# PowerSupply.net
KiCad netlist of a schematic drawn in Altium Designer
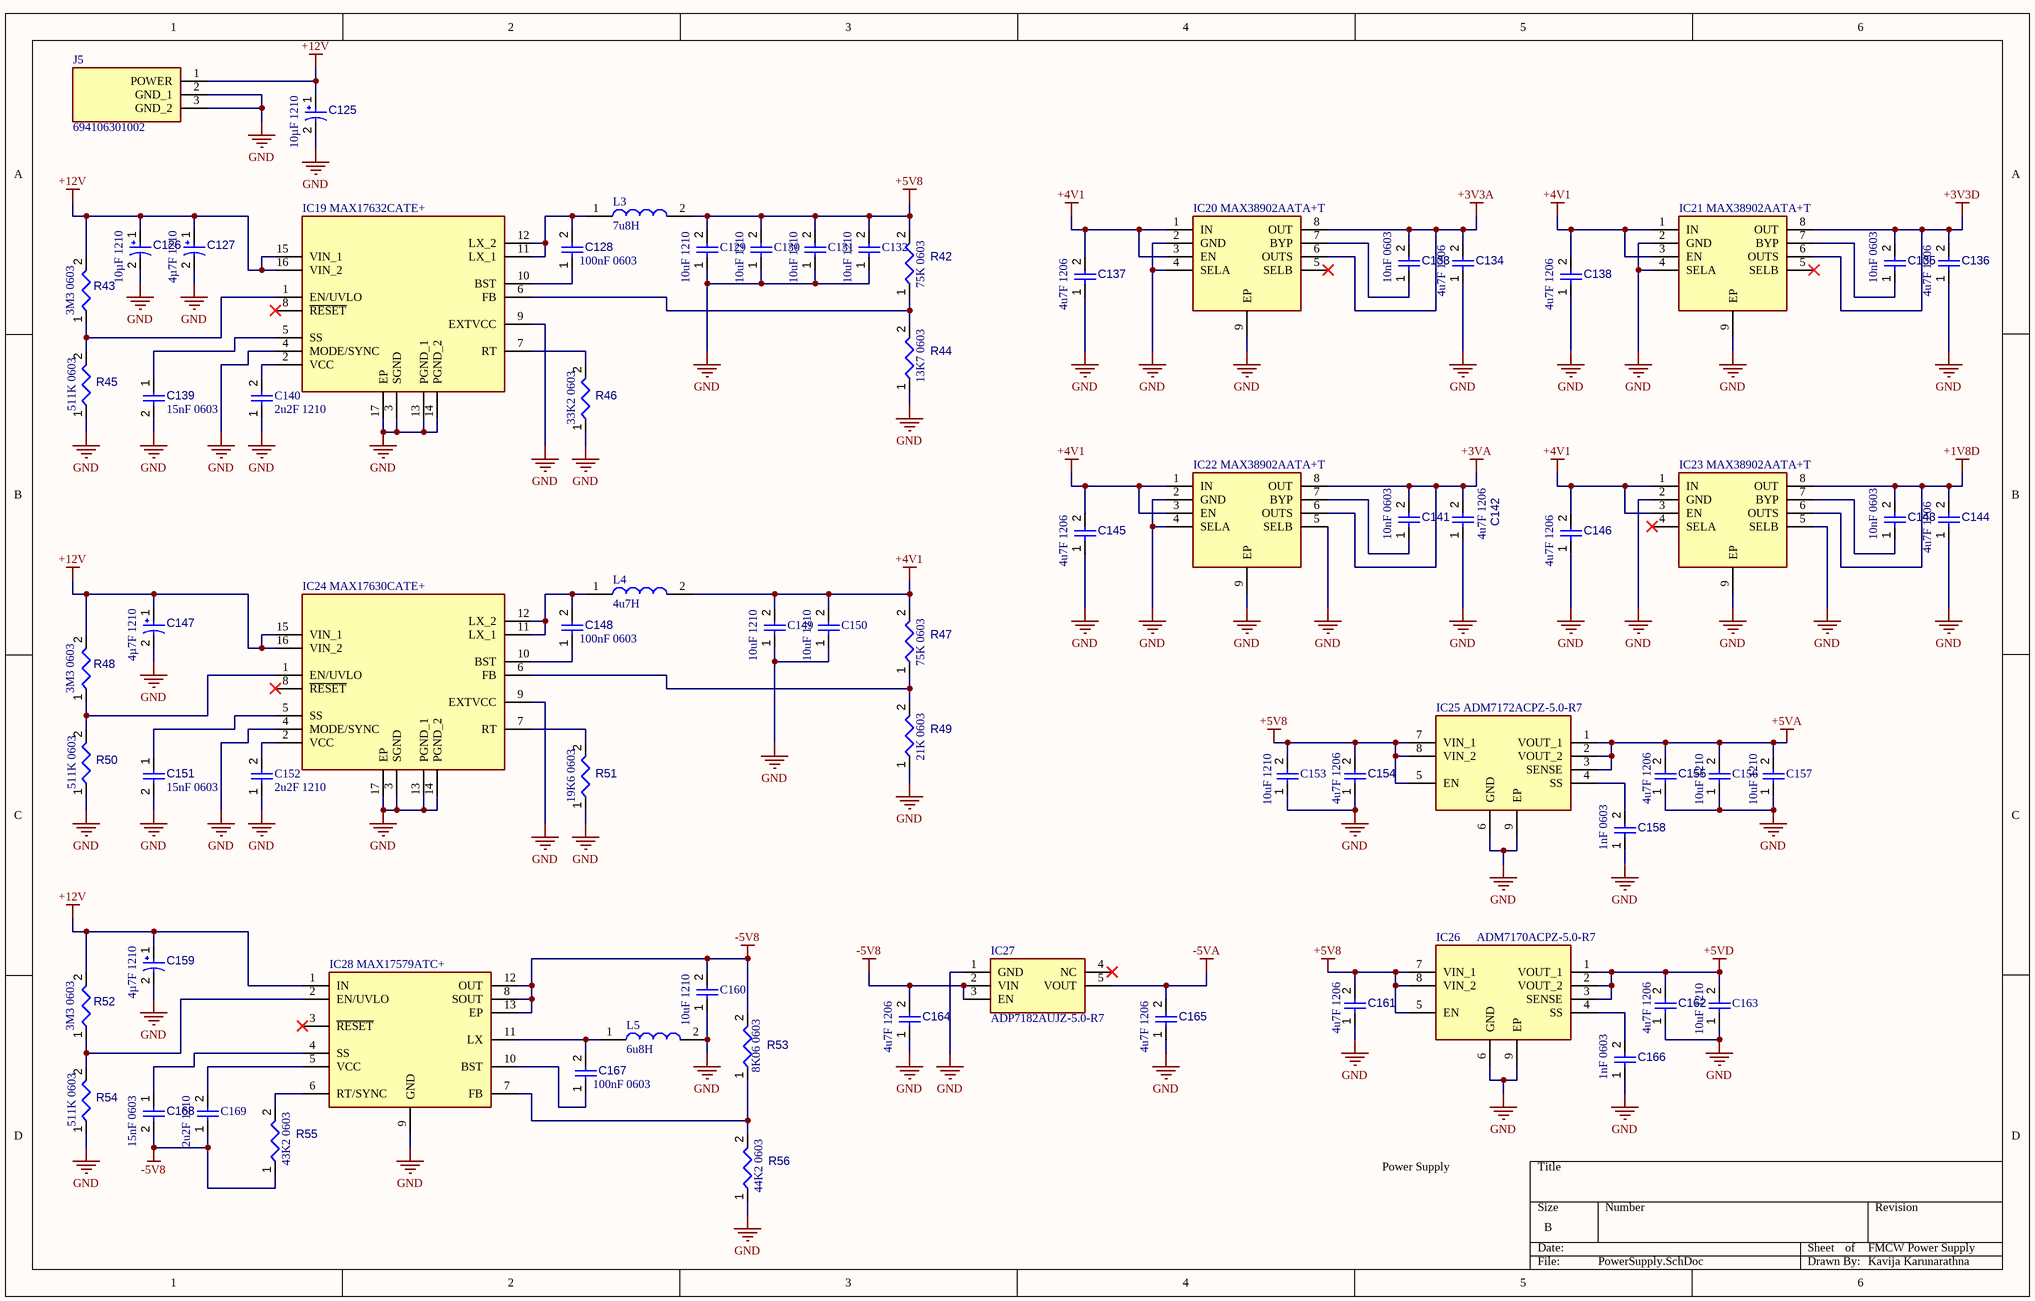
[diagram p0: PowerSupply.SchDoc]

(export (version "E")
  (design (tool "Eeschema 10.0.6"))
  (components
    (comp (ref "C125")
      (value "10µF 1210")
      (footprint "AVX-TAJ-B-2_N")
      (description "Tantalum Capacitors - Solid SMD 20V 10uF 10% 1210 ES R = 2.1 Ohm")
      (fields (field (name "MANUFACTURER") "AVX") (field (name "TOLERANCE") "10%"))
      (libsource (lib "Kavija Karunarathna") (part "CAP-P-2"))
    )
    (comp (ref "C126")
      (value "10µF 1210")
      (footprint "AVX-TAJ-B-2_N")
      (description "Tantalum Capacitors - Solid SMD 20V 10uF 10% 1210 ES R = 2.1 Ohm")
      (fields (field (name "MANUFACTURER") "AVX") (field (name "TOLERANCE") "10%"))
      (libsource (lib "Kavija Karunarathna") (part "CAP-P-2"))
    )
    (comp (ref "C127")
      (value "4µ7F 1210")
      (footprint "AVX-TAJ-B-2_N")
      (description "Tantalum Capacitors - Solid SMD 20V 4.7uF 10% 1210 E SR= 3 Ohm")
      (fields (field (name "MANUFACTURER") "AVX") (field (name "TOLERANCE") "10%"))
      (libsource (lib "Kavija Karunarathna") (part "CAP-P-2"))
    )
    (comp (ref "C128")
      (value "100nF 0603")
      (footprint "CAPC0603(1608)100_L")
      (description "Chip Capacitor, 1µF +/-0.1%, 25V, 0603, Thickness 1 mm")
      (fields (field (name "TOLERANCE") "20%") (field (name "MANUFACTURER PART NO") "0603X104K250CT"))
      (libsource (lib "Kavija Karunarathna") (part "CAP-NP-2"))
    )
    (comp (ref "C129")
      (value "10uF 1210")
      (footprint "CAPC3225X279N")
      (description "Multilayer Ceramic Capacitors MLCC - SMD/SMT 100V 2.2uF X7R 1210 5% AEC-Q200")
      (fields
        (field (name "MANUFACTURER PART NO") "C1210C106K6PACTU")
        (field (name "MOUSER PART NO") "80-C1210C106K6P")
      )
      (libsource (lib "SchLib") (part "12105C475K4Z2A"))
    )
    (comp (ref "C130")
      (value "10uF 1210")
      (footprint "CAPC3225X279N")
      (description "Multilayer Ceramic Capacitors MLCC - SMD/SMT 100V 2.2uF X7R 1210 5% AEC-Q200")
      (fields
        (field (name "MANUFACTURER PART NO") "C1210C106K6PACTU")
        (field (name "MOUSER PART NO") "80-C1210C106K6P")
      )
      (libsource (lib "SchLib") (part "12105C475K4Z2A"))
    )
    (comp (ref "C131")
      (value "10uF 1210")
      (footprint "CAPC3225X279N")
      (description "Multilayer Ceramic Capacitors MLCC - SMD/SMT 100V 2.2uF X7R 1210 5% AEC-Q200")
      (fields
        (field (name "MANUFACTURER PART NO") "C1210C106K6PACTU")
        (field (name "MOUSER PART NO") "80-C1210C106K6P")
      )
      (libsource (lib "SchLib") (part "12105C475K4Z2A"))
    )
    (comp (ref "C132")
      (value "10uF 1210")
      (footprint "CAPC3225X279N")
      (description "Multilayer Ceramic Capacitors MLCC - SMD/SMT 100V 2.2uF X7R 1210 5% AEC-Q200")
      (fields
        (field (name "MANUFACTURER PART NO") "C1210C106K6PACTU")
        (field (name "MOUSER PART NO") "80-C1210C106K6P")
      )
      (libsource (lib "SchLib") (part "12105C475K4Z2A"))
    )
    (comp (ref "C133")
      (value "10nF 0603")
      (footprint "CAPC0603(1608)100_L")
      (description "Multilayer Ceramic Capacitors MLCC - SMD/SMT 0603 10nF 16volts X7R 10%")
      (fields (field (name "TOLERANCE") "20%") (field (name "MANUFACTURER PART NO") "VJ0603Y103KXJAC31X"))
      (libsource (lib "Kavija Karunarathna") (part "CAP-NP-2"))
    )
    (comp (ref "C134")
      (value "4u7F 1206")
      (footprint "CAPC3216X180X50NL20T25")
      (description "Chip Capacitor, 10 uF, +/- 10%, 16 V, 1206 (3216 Metric)")
      (fields (field (name "TOLERANCE") "10%") (field (name "MANUFACTURER PART NO") "CC1206KFX7R9BB475"))
      (libsource (lib "Kavija Karunarathna") (part "CAP-NP-2"))
    )
    (comp (ref "C135")
      (value "10nF 0603")
      (footprint "CAPC0603(1608)100_L")
      (description "Multilayer Ceramic Capacitors MLCC - SMD/SMT 0603 10nF 16volts X7R 10%")
      (fields (field (name "TOLERANCE") "20%") (field (name "MANUFACTURER PART NO") "VJ0603Y103KXJAC31X"))
      (libsource (lib "Kavija Karunarathna") (part "CAP-NP-2"))
    )
    (comp (ref "C136")
      (value "4u7F 1206")
      (footprint "CAPC3216X180X50NL20T25")
      (description "Chip Capacitor, 10 uF, +/- 10%, 16 V, 1206 (3216 Metric)")
      (fields (field (name "TOLERANCE") "10%") (field (name "MANUFACTURER PART NO") "CC1206KFX7R9BB475"))
      (libsource (lib "Kavija Karunarathna") (part "CAP-NP-2"))
    )
    (comp (ref "C137")
      (value "4u7F 1206")
      (footprint "CAPC3216X180X50NL20T25")
      (description "Chip Capacitor, 10 uF, +/- 10%, 16 V, 1206 (3216 Metric)")
      (fields (field (name "TOLERANCE") "10%") (field (name "MANUFACTURER PART NO") "CC1206KFX7R9BB475"))
      (libsource (lib "Kavija Karunarathna") (part "CAP-NP-2"))
    )
    (comp (ref "C138")
      (value "4u7F 1206")
      (footprint "CAPC3216X180X50NL20T25")
      (description "Chip Capacitor, 10 uF, +/- 10%, 16 V, 1206 (3216 Metric)")
      (fields (field (name "TOLERANCE") "10%") (field (name "MANUFACTURER PART NO") "CC1206KFX7R9BB475"))
      (libsource (lib "Kavija Karunarathna") (part "CAP-NP-2"))
    )
    (comp (ref "C139")
      (value "15nF 0603")
      (footprint "CAPC0603(1608)100_L")
      (description "Chip Capacitor, 1µF +/-0.1%, 25V, 0603, Thickness 1 mm")
      (fields (field (name "TOLERANCE") "20%") (field (name "MANUFACTURER PART NO") "VJ0603Y153KXJAC31X"))
      (libsource (lib "Kavija Karunarathna") (part "CAP-NP-2"))
    )
    (comp (ref "C140")
      (value "2u2F 1210")
      (footprint "CAPC3225X279N")
      (description "Multilayer Ceramic Capacitors MLCC - SMD/SMT 100V 2.2uF X7R 1210 5% AEC-Q200")
      (fields
        (field (name "MANUFACTURER PART NO") "C1210C225J1RACAUTO")
        (field (name "MOUSER PART NO") "80-C1210C225J1RAUTO")
      )
      (libsource (lib "SchLib") (part "12105C475K4Z2A"))
    )
    (comp (ref "C141")
      (value "10nF 0603")
      (footprint "CAPC0603(1608)100_L")
      (description "Multilayer Ceramic Capacitors MLCC - SMD/SMT 0603 10nF 16volts X7R 10%")
      (fields (field (name "TOLERANCE") "20%") (field (name "MANUFACTURER PART NO") "VJ0603Y103KXJAC31X"))
      (libsource (lib "Kavija Karunarathna") (part "CAP-NP-2"))
    )
    (comp (ref "C142")
      (value "4u7F 1206")
      (footprint "CAPC3216X180X50NL20T25")
      (description "Chip Capacitor, 10 uF, +/- 10%, 16 V, 1206 (3216 Metric)")
      (fields (field (name "TOLERANCE") "10%") (field (name "MANUFACTURER PART NO") "CC1206KFX7R9BB475"))
      (libsource (lib "Kavija Karunarathna") (part "CAP-NP-2"))
    )
    (comp (ref "C143")
      (value "10nF 0603")
      (footprint "CAPC0603(1608)100_L")
      (description "Multilayer Ceramic Capacitors MLCC - SMD/SMT 0603 10nF 16volts X7R 10%")
      (fields (field (name "TOLERANCE") "20%") (field (name "MANUFACTURER PART NO") "VJ0603Y103KXJAC31X"))
      (libsource (lib "Kavija Karunarathna") (part "CAP-NP-2"))
    )
    (comp (ref "C144")
      (value "4u7F 1206")
      (footprint "CAPC3216X180X50NL20T25")
      (description "Chip Capacitor, 10 uF, +/- 10%, 16 V, 1206 (3216 Metric)")
      (fields (field (name "TOLERANCE") "10%") (field (name "MANUFACTURER PART NO") "CC1206KFX7R9BB475"))
      (libsource (lib "Kavija Karunarathna") (part "CAP-NP-2"))
    )
    (comp (ref "C145")
      (value "4u7F 1206")
      (footprint "CAPC3216X180X50NL20T25")
      (description "Chip Capacitor, 10 uF, +/- 10%, 16 V, 1206 (3216 Metric)")
      (fields (field (name "TOLERANCE") "10%") (field (name "MANUFACTURER PART NO") "CC1206KFX7R9BB475"))
      (libsource (lib "Kavija Karunarathna") (part "CAP-NP-2"))
    )
    (comp (ref "C146")
      (value "4u7F 1206")
      (footprint "CAPC3216X180X50NL20T25")
      (description "Chip Capacitor, 10 uF, +/- 10%, 16 V, 1206 (3216 Metric)")
      (fields (field (name "TOLERANCE") "10%") (field (name "MANUFACTURER PART NO") "CC1206KFX7R9BB475"))
      (libsource (lib "Kavija Karunarathna") (part "CAP-NP-2"))
    )
    (comp (ref "C147")
      (value "4µ7F 1210")
      (footprint "AVX-TAJ-B-2_N")
      (description "Tantalum Capacitors - Solid SMD 20V 4.7uF 10% 1210 E SR= 3 Ohm")
      (fields (field (name "MANUFACTURER") "AVX") (field (name "TOLERANCE") "10%"))
      (libsource (lib "Kavija Karunarathna") (part "CAP-P-2"))
    )
    (comp (ref "C148")
      (value "100nF 0603")
      (footprint "CAPC0603(1608)100_L")
      (description "Chip Capacitor, 1µF +/-0.1%, 25V, 0603, Thickness 1 mm")
      (fields (field (name "TOLERANCE") "20%") (field (name "MANUFACTURER PART NO") "0603X104K250CT"))
      (libsource (lib "Kavija Karunarathna") (part "CAP-NP-2"))
    )
    (comp (ref "C149")
      (value "10uF 1210")
      (footprint "CAPC3225X279N")
      (description "Multilayer Ceramic Capacitors MLCC - SMD/SMT 100V 2.2uF X7R 1210 5% AEC-Q200")
      (fields
        (field (name "MANUFACTURER PART NO") "C1210C106K6PACTU")
        (field (name "MOUSER PART NO") "80-C1210C106K6P")
      )
      (libsource (lib "SchLib") (part "12105C475K4Z2A"))
    )
    (comp (ref "C150")
      (value "10uF 1210")
      (footprint "CAPC3225X279N")
      (description "Multilayer Ceramic Capacitors MLCC - SMD/SMT 100V 2.2uF X7R 1210 5% AEC-Q200")
      (fields
        (field (name "MANUFACTURER PART NO") "C1210C106K6PACTU")
        (field (name "MOUSER PART NO") "80-C1210C106K6P")
      )
      (libsource (lib "SchLib") (part "12105C475K4Z2A"))
    )
    (comp (ref "C151")
      (value "15nF 0603")
      (footprint "CAPC0603(1608)100_L")
      (description "Chip Capacitor, 1µF +/-0.1%, 25V, 0603, Thickness 1 mm")
      (fields (field (name "TOLERANCE") "20%") (field (name "MANUFACTURER PART NO") "VJ0603Y153KXJAC31X"))
      (libsource (lib "Kavija Karunarathna") (part "CAP-NP-2"))
    )
    (comp (ref "C152")
      (value "2u2F 1210")
      (footprint "CAPC3225X279N")
      (description "Multilayer Ceramic Capacitors MLCC - SMD/SMT 100V 2.2uF X7R 1210 5% AEC-Q200")
      (fields
        (field (name "MANUFACTURER PART NO") "C1210C225J1RACAUTO")
        (field (name "MOUSER PART NO") "80-C1210C225J1RAUTO")
      )
      (libsource (lib "SchLib") (part "12105C475K4Z2A"))
    )
    (comp (ref "C153")
      (value "10uF 1210")
      (footprint "CAPC3225X279N")
      (description "Multilayer Ceramic Capacitors MLCC - SMD/SMT 100V 2.2uF X7R 1210 5% AEC-Q200")
      (fields
        (field (name "MANUFACTURER PART NO") "C1210C106K6PACTU")
        (field (name "MOUSER PART NO") "80-C1210C106K6P")
      )
      (libsource (lib "SchLib") (part "12105C475K4Z2A"))
    )
    (comp (ref "C154")
      (value "4u7F 1206")
      (footprint "CAPC3216X180X50NL20T25")
      (description "Chip Capacitor, 10 uF, +/- 10%, 16 V, 1206 (3216 Metric)")
      (fields (field (name "TOLERANCE") "10%") (field (name "MANUFACTURER PART NO") "CC1206KFX7R9BB475"))
      (libsource (lib "Kavija Karunarathna") (part "CAP-NP-2"))
    )
    (comp (ref "C155")
      (value "4u7F 1206")
      (footprint "CAPC3216X180X50NL20T25")
      (description "Chip Capacitor, 10 uF, +/- 10%, 16 V, 1206 (3216 Metric)")
      (fields (field (name "TOLERANCE") "10%") (field (name "MANUFACTURER PART NO") "CC1206KFX7R9BB475"))
      (libsource (lib "Kavija Karunarathna") (part "CAP-NP-2"))
    )
    (comp (ref "C156")
      (value "10uF 1210")
      (footprint "CAPC3225X279N")
      (description "Multilayer Ceramic Capacitors MLCC - SMD/SMT 100V 2.2uF X7R 1210 5% AEC-Q200")
      (fields
        (field (name "MANUFACTURER PART NO") "C1210C106K6PACTU")
        (field (name "MOUSER PART NO") "80-C1210C106K6P")
      )
      (libsource (lib "SchLib") (part "12105C475K4Z2A"))
    )
    (comp (ref "C157")
      (value "10uF 1210")
      (footprint "CAPC3225X279N")
      (description "Multilayer Ceramic Capacitors MLCC - SMD/SMT 100V 2.2uF X7R 1210 5% AEC-Q200")
      (fields
        (field (name "MANUFACTURER PART NO") "C1210C106K6PACTU")
        (field (name "MOUSER PART NO") "80-C1210C106K6P")
      )
      (libsource (lib "SchLib") (part "12105C475K4Z2A"))
    )
    (comp (ref "C158")
      (value "1nF 0603")
      (footprint "CAPC0603(1608)100_L")
      (description "Multilayer Ceramic Capacitors MLCC - SMD/SMT 0603 10nF 16volts X7R 10%")
      (fields (field (name "TOLERANCE") "20%") (field (name "MANUFACTURER PART NO") "06035C102J4T4A"))
      (libsource (lib "Kavija Karunarathna") (part "CAP-NP-2"))
    )
    (comp (ref "C159")
      (value "4µ7F 1210")
      (footprint "AVX-TAJ-B-2_N")
      (description "Tantalum Capacitors - Solid SMD 20V 4.7uF 10% 1210 E SR= 3 Ohm")
      (fields (field (name "MANUFACTURER") "AVX") (field (name "TOLERANCE") "10%"))
      (libsource (lib "Kavija Karunarathna") (part "CAP-P-2"))
    )
    (comp (ref "C160")
      (value "10uF 1210")
      (footprint "CAPC3225X279N")
      (description "Multilayer Ceramic Capacitors MLCC - SMD/SMT 100V 2.2uF X7R 1210 5% AEC-Q200")
      (fields
        (field (name "MANUFACTURER PART NO") "C1210C106K6PACTU")
        (field (name "MOUSER PART NO") "80-C1210C106K6P")
      )
      (libsource (lib "SchLib") (part "12105C475K4Z2A"))
    )
    (comp (ref "C161")
      (value "4u7F 1206")
      (footprint "CAPC3216X180X50NL20T25")
      (description "Chip Capacitor, 10 uF, +/- 10%, 16 V, 1206 (3216 Metric)")
      (fields (field (name "TOLERANCE") "10%") (field (name "MANUFACTURER PART NO") "CC1206KFX7R9BB475"))
      (libsource (lib "Kavija Karunarathna") (part "CAP-NP-2"))
    )
    (comp (ref "C162")
      (value "4u7F 1206")
      (footprint "CAPC3216X180X50NL20T25")
      (description "Chip Capacitor, 10 uF, +/- 10%, 16 V, 1206 (3216 Metric)")
      (fields (field (name "TOLERANCE") "10%") (field (name "MANUFACTURER PART NO") "CC1206KFX7R9BB475"))
      (libsource (lib "Kavija Karunarathna") (part "CAP-NP-2"))
    )
    (comp (ref "C163")
      (value "10uF 1210")
      (footprint "CAPC3225X279N")
      (description "Multilayer Ceramic Capacitors MLCC - SMD/SMT 100V 2.2uF X7R 1210 5% AEC-Q200")
      (fields
        (field (name "MANUFACTURER PART NO") "C1210C106K6PACTU")
        (field (name "MOUSER PART NO") "80-C1210C106K6P")
      )
      (libsource (lib "SchLib") (part "12105C475K4Z2A"))
    )
    (comp (ref "C164")
      (value "4u7F 1206")
      (footprint "CAPC3216X180X50NL20T25")
      (description "Chip Capacitor, 10 uF, +/- 10%, 16 V, 1206 (3216 Metric)")
      (fields (field (name "TOLERANCE") "10%") (field (name "MANUFACTURER PART NO") "CC1206KFX7R9BB475"))
      (libsource (lib "Kavija Karunarathna") (part "CAP-NP-2"))
    )
    (comp (ref "C165")
      (value "4u7F 1206")
      (footprint "CAPC3216X180X50NL20T25")
      (description "Chip Capacitor, 10 uF, +/- 10%, 16 V, 1206 (3216 Metric)")
      (fields (field (name "TOLERANCE") "10%") (field (name "MANUFACTURER PART NO") "CC1206KFX7R9BB475"))
      (libsource (lib "Kavija Karunarathna") (part "CAP-NP-2"))
    )
    (comp (ref "C166")
      (value "1nF 0603")
      (footprint "CAPC0603(1608)100_L")
      (description "Multilayer Ceramic Capacitors MLCC - SMD/SMT 0603 10nF 16volts X7R 10%")
      (fields (field (name "TOLERANCE") "20%") (field (name "MANUFACTURER PART NO") "06035C102J4T4A"))
      (libsource (lib "Kavija Karunarathna") (part "CAP-NP-2"))
    )
    (comp (ref "C167")
      (value "100nF 0603")
      (footprint "CAPC0603(1608)100_L")
      (description "Chip Capacitor, 1µF +/-0.1%, 25V, 0603, Thickness 1 mm")
      (fields (field (name "TOLERANCE") "20%") (field (name "MANUFACTURER PART NO") "0603X104K250CT"))
      (libsource (lib "Kavija Karunarathna") (part "CAP-NP-2"))
    )
    (comp (ref "C168")
      (value "15nF 0603")
      (footprint "CAPC0603(1608)100_L")
      (description "Chip Capacitor, 1µF +/-0.1%, 25V, 0603, Thickness 1 mm")
      (fields (field (name "TOLERANCE") "20%") (field (name "MANUFACTURER PART NO") "VJ0603Y153KXJAC31X"))
      (libsource (lib "Kavija Karunarathna") (part "CAP-NP-2"))
    )
    (comp (ref "C169")
      (value "2u2F 1210")
      (footprint "CAPC3225X279N")
      (description "Multilayer Ceramic Capacitors MLCC - SMD/SMT 100V 2.2uF X7R 1210 5% AEC-Q200")
      (fields
        (field (name "MANUFACTURER PART NO") "C1210C225J1RACAUTO")
        (field (name "MOUSER PART NO") "80-C1210C225J1RAUTO")
      )
      (libsource (lib "SchLib") (part "12105C475K4Z2A"))
    )
    (comp (ref "IC19")
      (value "MAX17632CATE+")
      (footprint "QFN50P300X300X80-17N")
      (description "Integrated Circuit")
      (fields (field (name "MOUSER PART NO") "700-MAX17632CATE+"))
      (libsource (lib "SchLib") (part "MAX17632CATE+"))
    )
    (comp (ref "IC20")
      (value "MAX38902AATA+T")
      (footprint "SON50P200X200X80-9N-D")
      (description "Integrated Circuit")
      (fields (field (name "MOUSER PART NO") "700-MAX38902AATA+T"))
      (libsource (lib "SchLib") (part "MAX38902AATA+T"))
    )
    (comp (ref "IC21")
      (value "MAX38902AATA+T")
      (footprint "SON50P200X200X80-9N-D")
      (description "Integrated Circuit")
      (fields (field (name "MOUSER PART NO") "700-MAX38902AATA+T"))
      (libsource (lib "SchLib") (part "MAX38902AATA+T"))
    )
    (comp (ref "IC22")
      (value "MAX38902AATA+T")
      (footprint "SON50P200X200X80-9N-D")
      (description "Integrated Circuit")
      (fields (field (name "MOUSER PART NO") "700-MAX38902AATA+T"))
      (libsource (lib "SchLib") (part "MAX38902AATA+T"))
    )
    (comp (ref "IC23")
      (value "MAX38902AATA+T")
      (footprint "SON50P200X200X80-9N-D")
      (description "Integrated Circuit")
      (fields (field (name "MOUSER PART NO") "700-MAX38902AATA+T"))
      (libsource (lib "SchLib") (part "MAX38902AATA+T"))
    )
    (comp (ref "IC24")
      (value "MAX17630CATE+")
      (footprint "QFN50P300X300X80-17N")
      (description "Switching Voltage Regulators For MAX17631C: 4.5V to 36V, 1.5A, High-E")
      (fields (field (name "MOUSER PART NO") "700-MAX17630CATE+"))
      (libsource (lib "SchLib") (part "MAX17630CATE+"))
    )
    (comp (ref "IC25")
      (value "ADM7172ACPZ-5.0-R7")
      (footprint "SON50P300X300X80-9N-D")
      (description "Integrated Circuit")
      (fields (field (name "MOUSER PART NO") "584-ADM7172ACPZ5.0R7"))
      (libsource (lib "SchLib") (part "ADM7172ACPZ-5.0-R7"))
    )
    (comp (ref "IC26")
      (value "ADM7170ACPZ-5.0-R7")
      (footprint "SON50P300X300X80-9N-D")
      (description "Integrated Circuit")
      (fields (field (name "MOUSER PART NO") "584-ADM7170ACPZ5.0R7"))
      (libsource (lib "SchLib") (part "ADM7170ACPZ-5.0-R7"))
    )
    (comp (ref "IC27")
      (value "ADP7182AUJZ-5.0-R7")
      (footprint "SOT95P280X100-5N")
      (description "Integrated Circuit")
      (fields (field (name "MOUSER PART NO") "584-ADP7182AUJZ5.0R7"))
      (libsource (lib "SchLib") (part "ADP7182AUJZ-5.0-R7"))
    )
    (comp (ref "IC28")
      (value "MAX17579ATC+")
      (footprint "SON50P300X300X80-13N")
      (description "Integrated Circuit")
      (fields (field (name "MOUSER PART NO") "700-MAX17579ATC+"))
      (libsource (lib "SchLib") (part "MAX17579ATC+"))
    )
    (comp (ref "J5")
      (value "694106301002")
      (footprint "694106301002")
      (description "Connector")
      (fields (field (name "MOUSER PART NO") "710-694106301002"))
      (libsource (lib "SchLib") (part "694106301002"))
    )
    (comp (ref "L3")
      (value "7u8H")
      (footprint "SamacSys:INDPM135129X640N")
      (description "Inductor")
      (fields
        (field (name "MANUFACTURER PART NO") "IHLP5050FDER7R8M5A")
        (field (name "MOUSER PART NO") "70-IHLP5050FDR7R8M5A")
      )
      (libsource (lib "*") (part "IHLP5050FDER7R8M5A"))
    )
    (comp (ref "L4")
      (value "4u7H")
      (footprint "SamacSys:INDPM135129X640N")
      (description "Inductor")
      (fields
        (field (name "MANUFACTURER PART NO") "IHLP5050FDER4R7M5A")
        (field (name "MOUSER PART NO") "70-IHLP5050FDR4R7M5A")
      )
      (libsource (lib "*") (part "IHLP5050FDER4R7M5A"))
    )
    (comp (ref "L5")
      (value "6u8H")
      (footprint "SamacSys:SPM7054VC6R8MD")
      (description "Inductor")
      (fields
        (field (name "MANUFACTURER PART NO") "SPM7054VC-6R8M-D")
        (field (name "MOUSER PART NO") "810-SPM7054VC-6R8M-D")
      )
      (libsource (lib "*") (part "SPM7054VC-6R8M-D"))
    )
    (comp (ref "R42")
      (value "75K 0603")
      (footprint "RESC0603(1608)_L")
      (description "Thick Film Resistors - SMD General Purpose Chip Resistor 0603, 200Ohms, 1%, 1/10W")
      (fields (field (name "POWER") "100mW") (field (name "TOLERANCE") "5%"))
      (libsource (lib "Kavija Karunarathna") (part "120R3J"))
    )
    (comp (ref "R43")
      (value "3M3 0603")
      (footprint "RESC0603(1608)_L")
      (description "Thick Film Resistors - SMD 3.3 MOhms 100 mW (1/10 W) 0603 1 % AEC-Q200")
      (fields (field (name "POWER") "100mW") (field (name "TOLERANCE") "5%"))
      (libsource (lib "Kavija Karunarathna") (part "120R3J"))
    )
    (comp (ref "R44")
      (value "13K7 0603")
      (footprint "RESC0603(1608)_L")
      (description "Thick Film Resistors - SMD General Purpose Chip Resistor 0603, 200Ohms, 1%, 1/10W")
      (fields (field (name "POWER") "100mW") (field (name "TOLERANCE") "5%"))
      (libsource (lib "Kavija Karunarathna") (part "120R3J"))
    )
    (comp (ref "R45")
      (value "511K 0603")
      (footprint "RESC0603(1608)_L")
      (description "Thick Film Resistors - SMD General Purpose Chip Resistor 0603, 200Ohms, 1%, 1/10W")
      (fields (field (name "POWER") "100mW") (field (name "TOLERANCE") "5%"))
      (libsource (lib "Kavija Karunarathna") (part "120R3J"))
    )
    (comp (ref "R46")
      (value "33K2 0603")
      (footprint "RESC0603(1608)_L")
      (description "Thick Film Resistors - SMD General Purpose Chip Resistor 0603, 200Ohms, 1%, 1/10W")
      (fields (field (name "POWER") "100mW") (field (name "TOLERANCE") "5%"))
      (libsource (lib "Kavija Karunarathna") (part "120R3J"))
    )
    (comp (ref "R47")
      (value "75K 0603")
      (footprint "RESC0603(1608)_L")
      (description "Thick Film Resistors - SMD General Purpose Chip Resistor 0603, 200Ohms, 1%, 1/10W")
      (fields (field (name "POWER") "100mW") (field (name "TOLERANCE") "5%"))
      (libsource (lib "Kavija Karunarathna") (part "120R3J"))
    )
    (comp (ref "R48")
      (value "3M3 0603")
      (footprint "RESC0603(1608)_L")
      (description "Thick Film Resistors - SMD 3.3 MOhms 100 mW (1/10 W) 0603 1 % AEC-Q200")
      (fields (field (name "POWER") "100mW") (field (name "TOLERANCE") "5%"))
      (libsource (lib "Kavija Karunarathna") (part "120R3J"))
    )
    (comp (ref "R49")
      (value "21K 0603")
      (footprint "RESC0603(1608)_L")
      (description "Thick Film Resistors - SMD General Purpose Chip Resistor 0603, 200Ohms, 1%, 1/10W")
      (fields (field (name "POWER") "100mW") (field (name "TOLERANCE") "5%"))
      (libsource (lib "Kavija Karunarathna") (part "120R3J"))
    )
    (comp (ref "R50")
      (value "511K 0603")
      (footprint "RESC0603(1608)_L")
      (description "Thick Film Resistors - SMD General Purpose Chip Resistor 0603, 200Ohms, 1%, 1/10W")
      (fields (field (name "POWER") "100mW") (field (name "TOLERANCE") "5%"))
      (libsource (lib "Kavija Karunarathna") (part "120R3J"))
    )
    (comp (ref "R51")
      (value "19K6 0603")
      (footprint "RESC0603(1608)_L")
      (description "Thick Film Resistors - SMD General Purpose Chip Resistor 0603, 200Ohms, 1%, 1/10W")
      (fields (field (name "POWER") "100mW") (field (name "TOLERANCE") "5%"))
      (libsource (lib "Kavija Karunarathna") (part "120R3J"))
    )
    (comp (ref "R52")
      (value "3M3 0603")
      (footprint "RESC0603(1608)_L")
      (description "Thick Film Resistors - SMD 3.3 MOhms 100 mW (1/10 W) 0603 1 % AEC-Q200")
      (fields (field (name "POWER") "100mW") (field (name "TOLERANCE") "5%"))
      (libsource (lib "Kavija Karunarathna") (part "120R3J"))
    )
    (comp (ref "R53")
      (value "8K06 0603")
      (footprint "RESC0603(1608)_L")
      (description "Thin Film Resistors - SMD RN 0603 8K06 0.1% 10PPM")
      (fields (field (name "POWER") "100mW") (field (name "TOLERANCE") "5%"))
      (libsource (lib "Kavija Karunarathna") (part "120R3J"))
    )
    (comp (ref "R54")
      (value "511K 0603")
      (footprint "RESC0603(1608)_L")
      (description "Thick Film Resistors - SMD General Purpose Chip Resistor 0603, 200Ohms, 1%, 1/10W")
      (fields (field (name "POWER") "100mW") (field (name "TOLERANCE") "5%"))
      (libsource (lib "Kavija Karunarathna") (part "120R3J"))
    )
    (comp (ref "R55")
      (value "43K2 0603")
      (footprint "RESC0603(1608)_L")
      (description "Thick Film Resistors - SMD General Purpose Chip Resistor 0603, 200Ohms, 1%, 1/10W")
      (fields (field (name "POWER") "100mW") (field (name "TOLERANCE") "5%"))
      (libsource (lib "Kavija Karunarathna") (part "120R3J"))
    )
    (comp (ref "R56")
      (value "44K2 0603")
      (footprint "RESC0603(1608)_L")
      (description "Thick Film Resistors - SMD General Purpose Chip Resistor 0603, 200Ohms, 1%, 1/10W")
      (fields (field (name "POWER") "100mW") (field (name "TOLERANCE") "5%"))
      (libsource (lib "Kavija Karunarathna") (part "120R3J"))
    )
  )
  (nets
    (net (code "1") (name "+1V8D") (class "Default")
      (node (ref "C143") (pin "2") (pinfunction "2_2") (pintype "passive"))
      (node (ref "C144") (pin "2") (pinfunction "2_2") (pintype "passive"))
      (node (ref "IC23") (pin "6") (pinfunction "OUTS_6") (pintype "passive"))
      (node (ref "IC23") (pin "8") (pinfunction "OUT_8") (pintype "passive"))
    )
    (net (code "2") (name "+3V3A") (class "Default")
      (node (ref "C133") (pin "2") (pinfunction "2_2") (pintype "passive"))
      (node (ref "C134") (pin "2") (pinfunction "2_2") (pintype "passive"))
      (node (ref "IC20") (pin "6") (pinfunction "OUTS_6") (pintype "passive"))
      (node (ref "IC20") (pin "8") (pinfunction "OUT_8") (pintype "passive"))
    )
    (net (code "3") (name "+3V3D") (class "Default")
      (node (ref "C135") (pin "2") (pinfunction "2_2") (pintype "passive"))
      (node (ref "C136") (pin "2") (pinfunction "2_2") (pintype "passive"))
      (node (ref "IC21") (pin "6") (pinfunction "OUTS_6") (pintype "passive"))
      (node (ref "IC21") (pin "8") (pinfunction "OUT_8") (pintype "passive"))
    )
    (net (code "4") (name "+3VA") (class "Default")
      (node (ref "C141") (pin "2") (pinfunction "2_2") (pintype "passive"))
      (node (ref "C142") (pin "2") (pinfunction "2_2") (pintype "passive"))
      (node (ref "IC22") (pin "6") (pinfunction "OUTS_6") (pintype "passive"))
      (node (ref "IC22") (pin "8") (pinfunction "OUT_8") (pintype "passive"))
    )
    (net (code "5") (name "+4V1") (class "Default")
      (node (ref "C137") (pin "2") (pinfunction "2_2") (pintype "passive"))
      (node (ref "C138") (pin "2") (pinfunction "2_2") (pintype "passive"))
      (node (ref "C145") (pin "2") (pinfunction "2_2") (pintype "passive"))
      (node (ref "C146") (pin "2") (pinfunction "2_2") (pintype "passive"))
      (node (ref "C149") (pin "2") (pinfunction "2_2") (pintype "passive"))
      (node (ref "C150") (pin "2") (pinfunction "2_2") (pintype "passive"))
      (node (ref "IC20") (pin "1") (pinfunction "IN_1") (pintype "passive"))
      (node (ref "IC20") (pin "3") (pinfunction "EN_3") (pintype "passive"))
      (node (ref "IC21") (pin "1") (pinfunction "IN_1") (pintype "passive"))
      (node (ref "IC21") (pin "3") (pinfunction "EN_3") (pintype "passive"))
      (node (ref "IC22") (pin "1") (pinfunction "IN_1") (pintype "passive"))
      (node (ref "IC22") (pin "3") (pinfunction "EN_3") (pintype "passive"))
      (node (ref "IC23") (pin "1") (pinfunction "IN_1") (pintype "passive"))
      (node (ref "IC23") (pin "3") (pinfunction "EN_3") (pintype "passive"))
      (node (ref "L4") (pin "2") (pinfunction "2_2") (pintype "passive"))
      (node (ref "R47") (pin "2") (pinfunction "2_2") (pintype "passive"))
    )
    (net (code "6") (name "+5V8") (class "Default")
      (node (ref "C129") (pin "2") (pinfunction "2_2") (pintype "passive"))
      (node (ref "C130") (pin "2") (pinfunction "2_2") (pintype "passive"))
      (node (ref "C131") (pin "2") (pinfunction "2_2") (pintype "passive"))
      (node (ref "C132") (pin "2") (pinfunction "2_2") (pintype "passive"))
      (node (ref "C153") (pin "2") (pinfunction "2_2") (pintype "passive"))
      (node (ref "C154") (pin "2") (pinfunction "2_2") (pintype "passive"))
      (node (ref "C161") (pin "2") (pinfunction "2_2") (pintype "passive"))
      (node (ref "IC25") (pin "5") (pinfunction "EN_5") (pintype "passive"))
      (node (ref "IC25") (pin "7") (pinfunction "VIN_1_7") (pintype "passive"))
      (node (ref "IC25") (pin "8") (pinfunction "VIN_2_8") (pintype "passive"))
      (node (ref "IC26") (pin "5") (pinfunction "EN_5") (pintype "passive"))
      (node (ref "IC26") (pin "7") (pinfunction "VIN_1_7") (pintype "passive"))
      (node (ref "IC26") (pin "8") (pinfunction "VIN_2_8") (pintype "passive"))
      (node (ref "L3") (pin "2") (pinfunction "2_2") (pintype "passive"))
      (node (ref "R42") (pin "2") (pinfunction "2_2") (pintype "passive"))
    )
    (net (code "7") (name "+5VA") (class "Default")
      (node (ref "C155") (pin "2") (pinfunction "2_2") (pintype "passive"))
      (node (ref "C156") (pin "2") (pinfunction "2_2") (pintype "passive"))
      (node (ref "C157") (pin "2") (pinfunction "2_2") (pintype "passive"))
      (node (ref "IC25") (pin "1") (pinfunction "VOUT_1_1") (pintype "passive"))
      (node (ref "IC25") (pin "2") (pinfunction "VOUT_2_2") (pintype "passive"))
      (node (ref "IC25") (pin "3") (pinfunction "SENSE_3") (pintype "passive"))
    )
    (net (code "8") (name "+5VD") (class "Default")
      (node (ref "C162") (pin "2") (pinfunction "2_2") (pintype "passive"))
      (node (ref "C163") (pin "2") (pinfunction "2_2") (pintype "passive"))
      (node (ref "IC26") (pin "1") (pinfunction "VOUT_1_1") (pintype "passive"))
      (node (ref "IC26") (pin "2") (pinfunction "VOUT_2_2") (pintype "passive"))
      (node (ref "IC26") (pin "3") (pinfunction "SENSE_3") (pintype "passive"))
    )
    (net (code "9") (name "+12V") (class "Default")
      (node (ref "C125") (pin "1") (pinfunction "1_1") (pintype "passive"))
      (node (ref "C126") (pin "1") (pinfunction "1_1") (pintype "passive"))
      (node (ref "C127") (pin "1") (pinfunction "1_1") (pintype "passive"))
      (node (ref "C147") (pin "1") (pinfunction "1_1") (pintype "passive"))
      (node (ref "C159") (pin "1") (pinfunction "1_1") (pintype "passive"))
      (node (ref "IC19") (pin "15") (pinfunction "VIN_1_15") (pintype "passive"))
      (node (ref "IC19") (pin "16") (pinfunction "VIN_2_16") (pintype "passive"))
      (node (ref "IC24") (pin "15") (pinfunction "VIN_1_15") (pintype "passive"))
      (node (ref "IC24") (pin "16") (pinfunction "VIN_2_16") (pintype "passive"))
      (node (ref "IC28") (pin "1") (pinfunction "IN_1") (pintype "passive"))
      (node (ref "J5") (pin "1") (pinfunction "POWER_1") (pintype "passive"))
      (node (ref "R43") (pin "2") (pinfunction "2_2") (pintype "passive"))
      (node (ref "R48") (pin "2") (pinfunction "2_2") (pintype "passive"))
      (node (ref "R52") (pin "2") (pinfunction "2_2") (pintype "passive"))
    )
    (net (code "10") (name "-5V8") (class "Default")
      (node (ref "C160") (pin "2") (pinfunction "2_2") (pintype "passive"))
      (node (ref "C164") (pin "2") (pinfunction "2_2") (pintype "passive"))
      (node (ref "C168") (pin "2") (pinfunction "2_2") (pintype "passive"))
      (node (ref "C169") (pin "1") (pinfunction "1_1") (pintype "passive"))
      (node (ref "IC27") (pin "2") (pinfunction "VIN_2") (pintype "passive"))
      (node (ref "IC27") (pin "3") (pinfunction "EN_3") (pintype "passive"))
      (node (ref "IC28") (pin "12") (pinfunction "OUT_12") (pintype "passive"))
      (node (ref "IC28") (pin "13") (pinfunction "EP_13") (pintype "passive"))
      (node (ref "IC28") (pin "8") (pinfunction "SOUT_8") (pintype "passive"))
      (node (ref "R53") (pin "2") (pinfunction "2_2") (pintype "passive"))
      (node (ref "R55") (pin "1") (pinfunction "1_1") (pintype "passive"))
    )
    (net (code "11") (name "-5VA") (class "Default")
      (node (ref "C165") (pin "2") (pinfunction "2_2") (pintype "passive"))
      (node (ref "IC27") (pin "5") (pinfunction "VOUT_5") (pintype "passive"))
    )
    (net (code "12") (name "GND") (class "Default")
      (node (ref "C125") (pin "2") (pinfunction "2_2") (pintype "passive"))
      (node (ref "C126") (pin "2") (pinfunction "2_2") (pintype "passive"))
      (node (ref "C127") (pin "2") (pinfunction "2_2") (pintype "passive"))
      (node (ref "C129") (pin "1") (pinfunction "1_1") (pintype "passive"))
      (node (ref "C130") (pin "1") (pinfunction "1_1") (pintype "passive"))
      (node (ref "C131") (pin "1") (pinfunction "1_1") (pintype "passive"))
      (node (ref "C132") (pin "1") (pinfunction "1_1") (pintype "passive"))
      (node (ref "C134") (pin "1") (pinfunction "1_1") (pintype "passive"))
      (node (ref "C136") (pin "1") (pinfunction "1_1") (pintype "passive"))
      (node (ref "C137") (pin "1") (pinfunction "1_1") (pintype "passive"))
      (node (ref "C138") (pin "1") (pinfunction "1_1") (pintype "passive"))
      (node (ref "C139") (pin "2") (pinfunction "2_2") (pintype "passive"))
      (node (ref "C140") (pin "1") (pinfunction "1_1") (pintype "passive"))
      (node (ref "C142") (pin "1") (pinfunction "1_1") (pintype "passive"))
      (node (ref "C144") (pin "1") (pinfunction "1_1") (pintype "passive"))
      (node (ref "C145") (pin "1") (pinfunction "1_1") (pintype "passive"))
      (node (ref "C146") (pin "1") (pinfunction "1_1") (pintype "passive"))
      (node (ref "C147") (pin "2") (pinfunction "2_2") (pintype "passive"))
      (node (ref "C149") (pin "1") (pinfunction "1_1") (pintype "passive"))
      (node (ref "C150") (pin "1") (pinfunction "1_1") (pintype "passive"))
      (node (ref "C151") (pin "2") (pinfunction "2_2") (pintype "passive"))
      (node (ref "C152") (pin "1") (pinfunction "1_1") (pintype "passive"))
      (node (ref "C153") (pin "1") (pinfunction "1_1") (pintype "passive"))
      (node (ref "C154") (pin "1") (pinfunction "1_1") (pintype "passive"))
      (node (ref "C155") (pin "1") (pinfunction "1_1") (pintype "passive"))
      (node (ref "C156") (pin "1") (pinfunction "1_1") (pintype "passive"))
      (node (ref "C157") (pin "1") (pinfunction "1_1") (pintype "passive"))
      (node (ref "C158") (pin "1") (pinfunction "1_1") (pintype "passive"))
      (node (ref "C159") (pin "2") (pinfunction "2_2") (pintype "passive"))
      (node (ref "C160") (pin "1") (pinfunction "1_1") (pintype "passive"))
      (node (ref "C161") (pin "1") (pinfunction "1_1") (pintype "passive"))
      (node (ref "C162") (pin "1") (pinfunction "1_1") (pintype "passive"))
      (node (ref "C163") (pin "1") (pinfunction "1_1") (pintype "passive"))
      (node (ref "C164") (pin "1") (pinfunction "1_1") (pintype "passive"))
      (node (ref "C165") (pin "1") (pinfunction "1_1") (pintype "passive"))
      (node (ref "C166") (pin "1") (pinfunction "1_1") (pintype "passive"))
      (node (ref "IC19") (pin "13") (pinfunction "PGND_1_13") (pintype "passive"))
      (node (ref "IC19") (pin "14") (pinfunction "PGND_2_14") (pintype "passive"))
      (node (ref "IC19") (pin "17") (pinfunction "EP_17") (pintype "passive"))
      (node (ref "IC19") (pin "3") (pinfunction "SGND_3") (pintype "passive"))
      (node (ref "IC19") (pin "4") (pinfunction "MODE/SYNC_4") (pintype "passive"))
      (node (ref "IC19") (pin "9") (pinfunction "EXTVCC_9") (pintype "passive"))
      (node (ref "IC20") (pin "2") (pinfunction "GND_2") (pintype "passive"))
      (node (ref "IC20") (pin "4") (pinfunction "SELA_4") (pintype "passive"))
      (node (ref "IC20") (pin "9") (pinfunction "EP_9") (pintype "passive"))
      (node (ref "IC21") (pin "2") (pinfunction "GND_2") (pintype "passive"))
      (node (ref "IC21") (pin "4") (pinfunction "SELA_4") (pintype "passive"))
      (node (ref "IC21") (pin "9") (pinfunction "EP_9") (pintype "passive"))
      (node (ref "IC22") (pin "2") (pinfunction "GND_2") (pintype "passive"))
      (node (ref "IC22") (pin "4") (pinfunction "SELA_4") (pintype "passive"))
      (node (ref "IC22") (pin "5") (pinfunction "SELB_5") (pintype "passive"))
      (node (ref "IC22") (pin "9") (pinfunction "EP_9") (pintype "passive"))
      (node (ref "IC23") (pin "2") (pinfunction "GND_2") (pintype "passive"))
      (node (ref "IC23") (pin "5") (pinfunction "SELB_5") (pintype "passive"))
      (node (ref "IC23") (pin "9") (pinfunction "EP_9") (pintype "passive"))
      (node (ref "IC24") (pin "13") (pinfunction "PGND_1_13") (pintype "passive"))
      (node (ref "IC24") (pin "14") (pinfunction "PGND_2_14") (pintype "passive"))
      (node (ref "IC24") (pin "17") (pinfunction "EP_17") (pintype "passive"))
      (node (ref "IC24") (pin "3") (pinfunction "SGND_3") (pintype "passive"))
      (node (ref "IC24") (pin "4") (pinfunction "MODE/SYNC_4") (pintype "passive"))
      (node (ref "IC24") (pin "9") (pinfunction "EXTVCC_9") (pintype "passive"))
      (node (ref "IC25") (pin "6") (pinfunction "GND_6") (pintype "passive"))
      (node (ref "IC25") (pin "9") (pinfunction "EP_9") (pintype "passive"))
      (node (ref "IC26") (pin "6") (pinfunction "GND_6") (pintype "passive"))
      (node (ref "IC26") (pin "9") (pinfunction "EP_9") (pintype "passive"))
      (node (ref "IC27") (pin "1") (pinfunction "GND_1") (pintype "passive"))
      (node (ref "IC28") (pin "9") (pinfunction "GND_9") (pintype "passive"))
      (node (ref "J5") (pin "2") (pinfunction "GND_1_2") (pintype "passive"))
      (node (ref "J5") (pin "3") (pinfunction "GND_2_3") (pintype "passive"))
      (node (ref "L5") (pin "2") (pinfunction "2_2") (pintype "passive"))
      (node (ref "R44") (pin "1") (pinfunction "1_1") (pintype "passive"))
      (node (ref "R45") (pin "1") (pinfunction "1_1") (pintype "passive"))
      (node (ref "R46") (pin "1") (pinfunction "1_1") (pintype "passive"))
      (node (ref "R49") (pin "1") (pinfunction "1_1") (pintype "passive"))
      (node (ref "R50") (pin "1") (pinfunction "1_1") (pintype "passive"))
      (node (ref "R51") (pin "1") (pinfunction "1_1") (pintype "passive"))
      (node (ref "R54") (pin "1") (pinfunction "1_1") (pintype "passive"))
      (node (ref "R56") (pin "1") (pinfunction "1_1") (pintype "passive"))
    )
    (net (code "13") (name "Net-(IC19-BST)") (class "Default")
      (node (ref "C128") (pin "1") (pinfunction "1_1") (pintype "passive"))
      (node (ref "IC19") (pin "10") (pinfunction "BST_10") (pintype "passive"))
    )
    (net (code "14") (name "Net-(IC19-EN{slash}UVLO)") (class "Default")
      (node (ref "IC19") (pin "1") (pinfunction "EN/UVLO_1") (pintype "passive"))
      (node (ref "R43") (pin "1") (pinfunction "1_1") (pintype "passive"))
      (node (ref "R45") (pin "2") (pinfunction "2_2") (pintype "passive"))
    )
    (net (code "15") (name "Net-(IC19-FB)") (class "Default")
      (node (ref "IC19") (pin "6") (pinfunction "FB_6") (pintype "passive"))
      (node (ref "R42") (pin "1") (pinfunction "1_1") (pintype "passive"))
      (node (ref "R44") (pin "2") (pinfunction "2_2") (pintype "passive"))
    )
    (net (code "16") (name "Net-(IC19-LX_1)") (class "Default")
      (node (ref "C128") (pin "2") (pinfunction "2_2") (pintype "passive"))
      (node (ref "IC19") (pin "11") (pinfunction "LX_1_11") (pintype "passive"))
      (node (ref "IC19") (pin "12") (pinfunction "LX_2_12") (pintype "passive"))
      (node (ref "L3") (pin "1") (pinfunction "1_1") (pintype "passive"))
    )
    (net (code "17") (name "Net-(IC19-RT)") (class "Default")
      (node (ref "IC19") (pin "7") (pinfunction "RT_7") (pintype "passive"))
      (node (ref "R46") (pin "2") (pinfunction "2_2") (pintype "passive"))
    )
    (net (code "18") (name "Net-(IC19-SS)") (class "Default")
      (node (ref "C139") (pin "1") (pinfunction "1_1") (pintype "passive"))
      (node (ref "IC19") (pin "5") (pinfunction "SS_5") (pintype "passive"))
    )
    (net (code "19") (name "Net-(IC19-VCC)") (class "Default")
      (node (ref "C140") (pin "2") (pinfunction "2_2") (pintype "passive"))
      (node (ref "IC19") (pin "2") (pinfunction "VCC_2") (pintype "passive"))
    )
    (net (code "20") (name "Net-(IC20-BYP)") (class "Default")
      (node (ref "C133") (pin "1") (pinfunction "1_1") (pintype "passive"))
      (node (ref "IC20") (pin "7") (pinfunction "BYP_7") (pintype "passive"))
    )
    (net (code "21") (name "Net-(IC21-BYP)") (class "Default")
      (node (ref "C135") (pin "1") (pinfunction "1_1") (pintype "passive"))
      (node (ref "IC21") (pin "7") (pinfunction "BYP_7") (pintype "passive"))
    )
    (net (code "22") (name "Net-(IC22-BYP)") (class "Default")
      (node (ref "C141") (pin "1") (pinfunction "1_1") (pintype "passive"))
      (node (ref "IC22") (pin "7") (pinfunction "BYP_7") (pintype "passive"))
    )
    (net (code "23") (name "Net-(IC23-BYP)") (class "Default")
      (node (ref "C143") (pin "1") (pinfunction "1_1") (pintype "passive"))
      (node (ref "IC23") (pin "7") (pinfunction "BYP_7") (pintype "passive"))
    )
    (net (code "24") (name "Net-(IC24-BST)") (class "Default")
      (node (ref "C148") (pin "1") (pinfunction "1_1") (pintype "passive"))
      (node (ref "IC24") (pin "10") (pinfunction "BST_10") (pintype "passive"))
    )
    (net (code "25") (name "Net-(IC24-EN{slash}UVLO)") (class "Default")
      (node (ref "IC24") (pin "1") (pinfunction "EN/UVLO_1") (pintype "passive"))
      (node (ref "R48") (pin "1") (pinfunction "1_1") (pintype "passive"))
      (node (ref "R50") (pin "2") (pinfunction "2_2") (pintype "passive"))
    )
    (net (code "26") (name "Net-(IC24-FB)") (class "Default")
      (node (ref "IC24") (pin "6") (pinfunction "FB_6") (pintype "passive"))
      (node (ref "R47") (pin "1") (pinfunction "1_1") (pintype "passive"))
      (node (ref "R49") (pin "2") (pinfunction "2_2") (pintype "passive"))
    )
    (net (code "27") (name "Net-(IC24-LX_1)") (class "Default")
      (node (ref "C148") (pin "2") (pinfunction "2_2") (pintype "passive"))
      (node (ref "IC24") (pin "11") (pinfunction "LX_1_11") (pintype "passive"))
      (node (ref "IC24") (pin "12") (pinfunction "LX_2_12") (pintype "passive"))
      (node (ref "L4") (pin "1") (pinfunction "1_1") (pintype "passive"))
    )
    (net (code "28") (name "Net-(IC24-RT)") (class "Default")
      (node (ref "IC24") (pin "7") (pinfunction "RT_7") (pintype "passive"))
      (node (ref "R51") (pin "2") (pinfunction "2_2") (pintype "passive"))
    )
    (net (code "29") (name "Net-(IC24-SS)") (class "Default")
      (node (ref "C151") (pin "1") (pinfunction "1_1") (pintype "passive"))
      (node (ref "IC24") (pin "5") (pinfunction "SS_5") (pintype "passive"))
    )
    (net (code "30") (name "Net-(IC24-VCC)") (class "Default")
      (node (ref "C152") (pin "2") (pinfunction "2_2") (pintype "passive"))
      (node (ref "IC24") (pin "2") (pinfunction "VCC_2") (pintype "passive"))
    )
    (net (code "31") (name "Net-(IC25-SS)") (class "Default")
      (node (ref "C158") (pin "2") (pinfunction "2_2") (pintype "passive"))
      (node (ref "IC25") (pin "4") (pinfunction "SS_4") (pintype "passive"))
    )
    (net (code "32") (name "Net-(IC26-SS)") (class "Default")
      (node (ref "C166") (pin "2") (pinfunction "2_2") (pintype "passive"))
      (node (ref "IC26") (pin "4") (pinfunction "SS_4") (pintype "passive"))
    )
    (net (code "33") (name "Net-(IC28-BST)") (class "Default")
      (node (ref "C167") (pin "1") (pinfunction "1_1") (pintype "passive"))
      (node (ref "IC28") (pin "10") (pinfunction "BST_10") (pintype "passive"))
    )
    (net (code "34") (name "Net-(IC28-EN{slash}UVLO)") (class "Default")
      (node (ref "IC28") (pin "2") (pinfunction "EN/UVLO_2") (pintype "passive"))
      (node (ref "R52") (pin "1") (pinfunction "1_1") (pintype "passive"))
      (node (ref "R54") (pin "2") (pinfunction "2_2") (pintype "passive"))
    )
    (net (code "35") (name "Net-(IC28-FB)") (class "Default")
      (node (ref "IC28") (pin "7") (pinfunction "FB_7") (pintype "passive"))
      (node (ref "R53") (pin "1") (pinfunction "1_1") (pintype "passive"))
      (node (ref "R56") (pin "2") (pinfunction "2_2") (pintype "passive"))
    )
    (net (code "36") (name "Net-(IC28-LX)") (class "Default")
      (node (ref "C167") (pin "2") (pinfunction "2_2") (pintype "passive"))
      (node (ref "IC28") (pin "11") (pinfunction "LX_11") (pintype "passive"))
      (node (ref "L5") (pin "1") (pinfunction "1_1") (pintype "passive"))
    )
    (net (code "37") (name "Net-(IC28-RT{slash}SYNC)") (class "Default")
      (node (ref "IC28") (pin "6") (pinfunction "RT/SYNC_6") (pintype "passive"))
      (node (ref "R55") (pin "2") (pinfunction "2_2") (pintype "passive"))
    )
    (net (code "38") (name "Net-(IC28-SS)") (class "Default")
      (node (ref "C168") (pin "1") (pinfunction "1_1") (pintype "passive"))
      (node (ref "IC28") (pin "4") (pinfunction "SS_4") (pintype "passive"))
    )
    (net (code "39") (name "Net-(IC28-VCC)") (class "Default")
      (node (ref "C169") (pin "2") (pinfunction "2_2") (pintype "passive"))
      (node (ref "IC28") (pin "5") (pinfunction "VCC_5") (pintype "passive"))
    )
    (net (code "40") (name "unconnected-(IC19-~{RESET}-Pad8)") (class "Default")
      (node (ref "IC19") (pin "8") (pinfunction "~{RESET}_8") (pintype "passive+no_connect"))
    )
    (net (code "41") (name "unconnected-(IC20-SELB-Pad5)") (class "Default")
      (node (ref "IC20") (pin "5") (pinfunction "SELB_5") (pintype "passive+no_connect"))
    )
    (net (code "42") (name "unconnected-(IC21-SELB-Pad5)") (class "Default")
      (node (ref "IC21") (pin "5") (pinfunction "SELB_5") (pintype "passive+no_connect"))
    )
    (net (code "43") (name "unconnected-(IC23-SELA-Pad4)") (class "Default")
      (node (ref "IC23") (pin "4") (pinfunction "SELA_4") (pintype "passive+no_connect"))
    )
    (net (code "44") (name "unconnected-(IC24-~{RESET}-Pad8)") (class "Default")
      (node (ref "IC24") (pin "8") (pinfunction "~{RESET}_8") (pintype "passive+no_connect"))
    )
    (net (code "45") (name "unconnected-(IC27-NC-Pad4)") (class "Default")
      (node (ref "IC27") (pin "4") (pinfunction "NC_4") (pintype "passive+no_connect"))
    )
    (net (code "46") (name "unconnected-(IC28-~{RESET}-Pad3)") (class "Default")
      (node (ref "IC28") (pin "3") (pinfunction "~{RESET}_3") (pintype "passive+no_connect"))
    )
  )
)
